# SWD-IR-SMD-V01-001.net
KiCad netlist of a schematic drawn in EAGLE
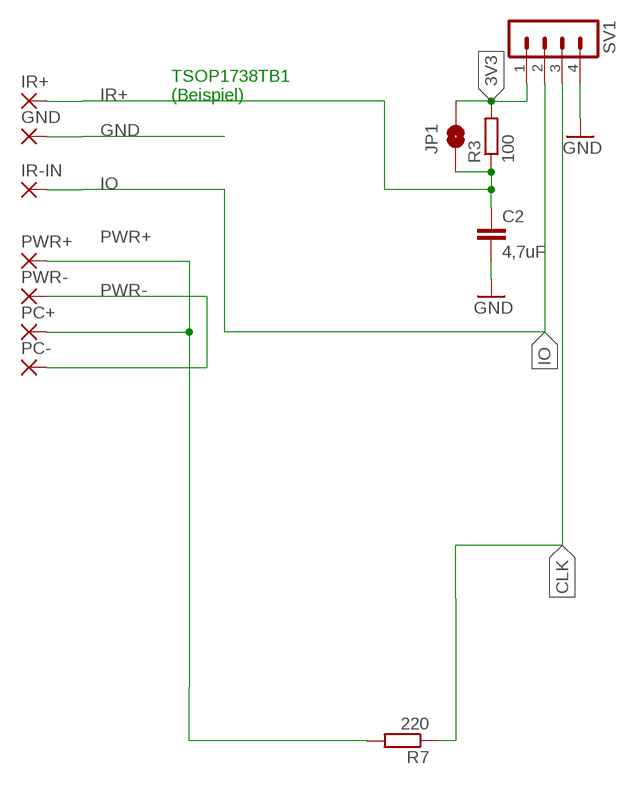
[diagram p0: schematic, sheet 1]

(export (version "E")
  (design (tool "Eeschema 10.0.6"))
  (components
    (comp (ref "C2")
      (value "4,7uF")
      (footprint "eagle-import:C1206K")
      (libsource (lib "eagle-import") (part "C-EUC1206K"))
    )
    (comp (ref "GND")
      (value "SMD2")
      (footprint "eagle-import:SMD1,27-2,54")
      (libsource (lib "eagle-import") (part "SMD2"))
    )
    (comp (ref "IR+")
      (value "SMD2")
      (footprint "eagle-import:SMD1,27-2,54")
      (libsource (lib "eagle-import") (part "SMD2"))
    )
    (comp (ref "IR-IN")
      (value "SMD2")
      (footprint "eagle-import:SMD1,27-2,54")
      (libsource (lib "eagle-import") (part "SMD2"))
    )
    (comp (ref "JP1")
      (value "JUMPER-SMT_2_NO_NO-SILK")
      (footprint "eagle-import:SMT-JUMPER_2_NO_NO-SILK")
      (libsource (lib "eagle-import") (part "JUMPER-SMT_2_NO_NO-SILK"))
    )
    (comp (ref "PC+")
      (value "SMD2")
      (footprint "eagle-import:SMD1,27-2,54")
      (libsource (lib "eagle-import") (part "SMD2"))
    )
    (comp (ref "PC-")
      (value "SMD2")
      (footprint "eagle-import:SMD1,27-2,54")
      (libsource (lib "eagle-import") (part "SMD2"))
    )
    (comp (ref "PWR+")
      (value "SMD2")
      (footprint "eagle-import:SMD1,27-2,54")
      (libsource (lib "eagle-import") (part "SMD2"))
    )
    (comp (ref "PWR-")
      (value "SMD2")
      (footprint "eagle-import:SMD1,27-2,54")
      (libsource (lib "eagle-import") (part "SMD2"))
    )
    (comp (ref "R3")
      (value "100")
      (footprint "eagle-import:R0805W")
      (libsource (lib "eagle-import") (part "R-EU_R0805W"))
    )
    (comp (ref "R7")
      (value "220")
      (footprint "eagle-import:R0805W")
      (libsource (lib "eagle-import") (part "R-EU_R0805W"))
    )
    (comp (ref "SV1")
      (value "MA04-1")
      (footprint "eagle-import:MA04-1")
      (libsource (lib "eagle-import") (part "MA04-1"))
    )
  )
  (nets
    (net (code "1") (name "/IR+") (class "Default")
      (node (ref "C2") (pin "1") (pinfunction "1_1") (pintype "passive"))
      (node (ref "IR+") (pin "1") (pinfunction "P_1") (pintype "passive"))
      (node (ref "JP1") (pin "1") (pinfunction "1_1") (pintype "passive"))
      (node (ref "R3") (pin "1") (pinfunction "1_1") (pintype "passive"))
    )
    (net (code "2") (name "/PWR+") (class "Default")
      (node (ref "PC+") (pin "1") (pinfunction "P_1") (pintype "passive"))
      (node (ref "PWR+") (pin "1") (pinfunction "P_1") (pintype "passive"))
      (node (ref "R7") (pin "2") (pinfunction "2_2") (pintype "passive"))
    )
    (net (code "3") (name "/PWR-") (class "Default")
      (node (ref "PC-") (pin "1") (pinfunction "P_1") (pintype "passive"))
      (node (ref "PWR-") (pin "1") (pinfunction "P_1") (pintype "passive"))
    )
    (net (code "4") (name "3V3") (class "Default")
      (node (ref "JP1") (pin "2") (pinfunction "2_2") (pintype "passive"))
      (node (ref "R3") (pin "2") (pinfunction "2_2") (pintype "passive"))
      (node (ref "SV1") (pin "1") (pinfunction "1_1") (pintype "passive"))
    )
    (net (code "5") (name "CLK") (class "Default")
      (node (ref "R7") (pin "1") (pinfunction "1_1") (pintype "passive"))
      (node (ref "SV1") (pin "3") (pinfunction "3_3") (pintype "passive"))
    )
    (net (code "6") (name "GND") (class "Default")
      (node (ref "C2") (pin "2") (pinfunction "2_2") (pintype "passive"))
      (node (ref "GND") (pin "1") (pinfunction "P_1") (pintype "passive"))
      (node (ref "SV1") (pin "4") (pinfunction "4_4") (pintype "passive"))
    )
    (net (code "7") (name "IO") (class "Default")
      (node (ref "IR-IN") (pin "1") (pinfunction "P_1") (pintype "passive"))
      (node (ref "SV1") (pin "2") (pinfunction "2_2") (pintype "passive"))
    )
  )
)
